# PIC.net
KiCad netlist of a schematic drawn in Altium Designer
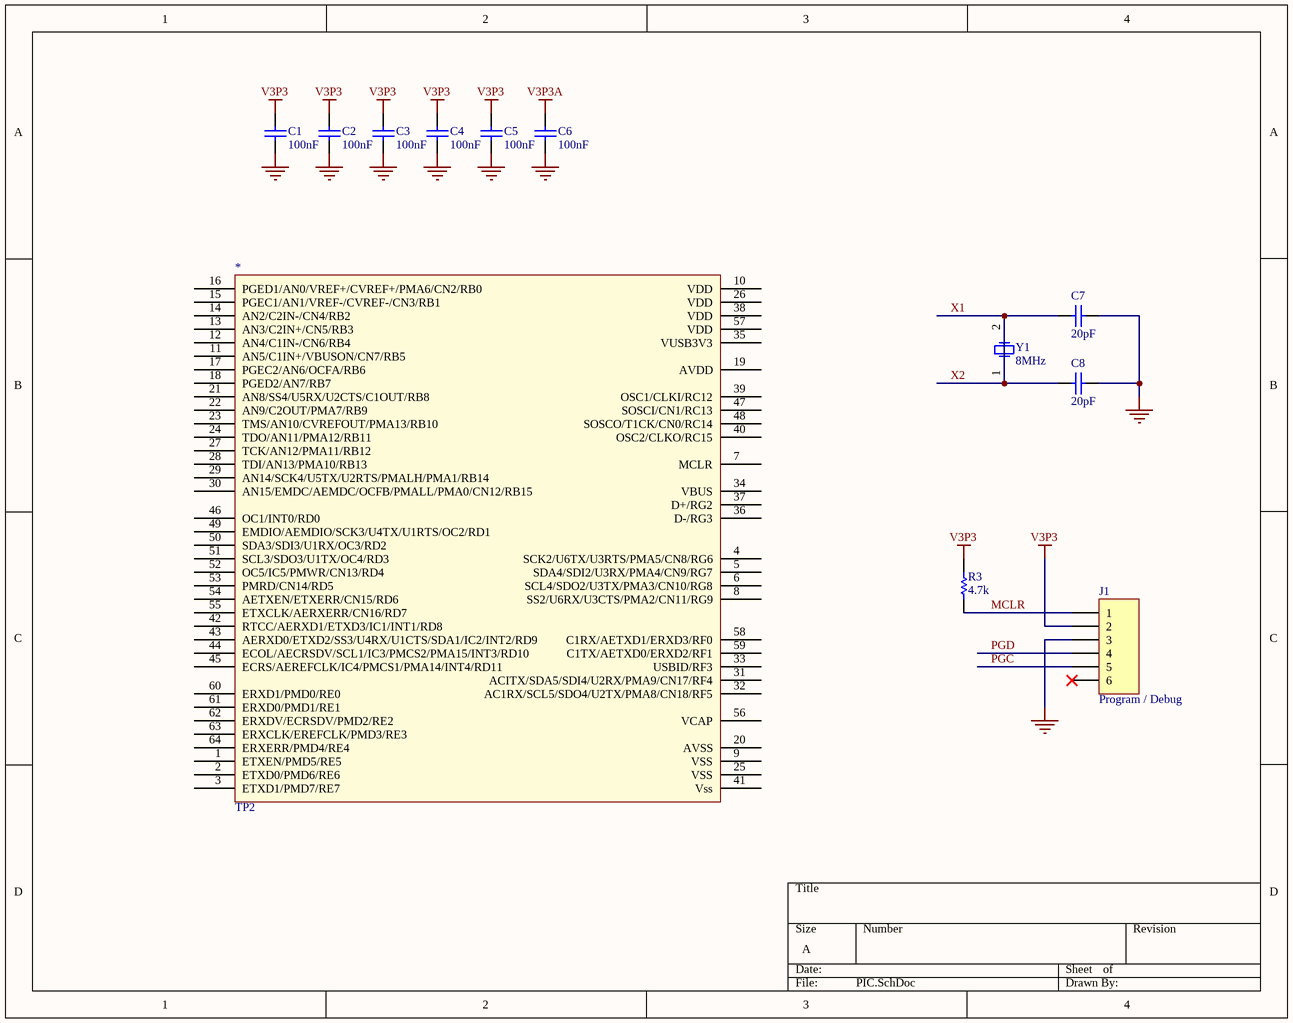
[diagram p0: PIC.SchDoc]

(export (version "E")
  (design (tool "Eeschema 10.0.6"))
  (components
    (comp (ref "*") (value "TP2") (libsource (lib "Rectangle-et-texte-PIC32") (part "TP2")))
    (comp (ref "C1")
      (value "100nF")
      (footprint "CAPC1608N")
      (description "Capacitor")
      (fields (field (name "PUBLISHER") "Altium Limited"))
      (libsource (lib "Miscellaneous Devices") (part "Cap"))
    )
    (comp (ref "C2")
      (value "100nF")
      (footprint "CAPC1608N")
      (description "Capacitor")
      (fields (field (name "PUBLISHER") "Altium Limited"))
      (libsource (lib "Miscellaneous Devices") (part "Cap"))
    )
    (comp (ref "C3")
      (value "100nF")
      (footprint "CAPC1608N")
      (description "Capacitor")
      (fields (field (name "PUBLISHER") "Altium Limited"))
      (libsource (lib "Miscellaneous Devices") (part "Cap"))
    )
    (comp (ref "C4")
      (value "100nF")
      (footprint "CAPC1608N")
      (description "Capacitor")
      (fields (field (name "PUBLISHER") "Altium Limited"))
      (libsource (lib "Miscellaneous Devices") (part "Cap"))
    )
    (comp (ref "C5")
      (value "100nF")
      (footprint "CAPC1608N")
      (description "Capacitor")
      (fields (field (name "PUBLISHER") "Altium Limited"))
      (libsource (lib "Miscellaneous Devices") (part "Cap"))
    )
    (comp (ref "C6")
      (value "100nF")
      (footprint "CAPC1608N")
      (description "Capacitor")
      (fields (field (name "PUBLISHER") "Altium Limited"))
      (libsource (lib "Miscellaneous Devices") (part "Cap"))
    )
    (comp (ref "C7")
      (value "20pF")
      (footprint "CAPC1005N")
      (description "Capacitor")
      (fields (field (name "PUBLISHER") "Altium Limited"))
      (libsource (lib "Miscellaneous Devices") (part "Cap"))
    )
    (comp (ref "C8")
      (value "20pF")
      (footprint "CAPC1005N")
      (description "Capacitor")
      (fields (field (name "PUBLISHER") "Altium Limited"))
      (libsource (lib "Miscellaneous Devices") (part "Cap"))
    )
    (comp (ref "J1")
      (value "Program / Debug")
      (footprint "MOLEX 6P 1.25 CMS")
      (description "Header, 6-Pin, Right Angle")
      (fields (field (name "PUBLISHER") "Altium Limited"))
      (libsource (lib "Miscellaneous Connectors") (part "Header 6H"))
    )
    (comp (ref "R3")
      (value "4.7k")
      (footprint "RESC1608N")
      (description "Resistor")
      (fields (field (name "PUBLISHER") "Altium Limited"))
      (libsource (lib "Miscellaneous Devices") (part "Res1"))
    )
    (comp (ref "Y1")
      (value "8MHz")
      (footprint "XTAL139X50X45")
      (description "Crystal Oscillator")
      (fields (field (name "PUBLISHER") "Altium Limited"))
      (libsource (lib "Miscellaneous Devices") (part "XTAL"))
    )
  )
  (nets
    (net (code "1") (name "/MCLR") (class "Default")
      (node (ref "J1") (pin "1") (pinfunction "1_1") (pintype "passive"))
      (node (ref "R3") (pin "1") (pinfunction "1_1") (pintype "passive"))
    )
    (net (code "2") (name "/PGC") (class "Default")
      (node (ref "J1") (pin "5") (pinfunction "5_5") (pintype "passive"))
    )
    (net (code "3") (name "/PGD") (class "Default")
      (node (ref "J1") (pin "4") (pinfunction "4_4") (pintype "passive"))
    )
    (net (code "4") (name "/X1") (class "Default")
      (node (ref "C7") (pin "1") (pinfunction "1_1") (pintype "passive"))
      (node (ref "C8") (pin "1") (pinfunction "1_1") (pintype "passive"))
      (node (ref "Y1") (pin "1") (pinfunction "OSC1_1") (pintype "passive"))
      (node (ref "Y1") (pin "2") (pinfunction "OSC2_2") (pintype "passive"))
    )
    (net (code "5") (name "GND") (class "Default")
      (node (ref "C1") (pin "1") (pinfunction "1_1") (pintype "passive"))
      (node (ref "C2") (pin "1") (pinfunction "1_1") (pintype "passive"))
      (node (ref "C3") (pin "1") (pinfunction "1_1") (pintype "passive"))
      (node (ref "C4") (pin "1") (pinfunction "1_1") (pintype "passive"))
      (node (ref "C5") (pin "1") (pinfunction "1_1") (pintype "passive"))
      (node (ref "C6") (pin "1") (pinfunction "1_1") (pintype "passive"))
      (node (ref "C7") (pin "2") (pinfunction "2_2") (pintype "passive"))
      (node (ref "C8") (pin "2") (pinfunction "2_2") (pintype "passive"))
      (node (ref "J1") (pin "3") (pinfunction "3_3") (pintype "passive"))
    )
    (net (code "6") (name "V3P3") (class "Default")
      (node (ref "C1") (pin "2") (pinfunction "2_2") (pintype "passive"))
      (node (ref "C2") (pin "2") (pinfunction "2_2") (pintype "passive"))
      (node (ref "C3") (pin "2") (pinfunction "2_2") (pintype "passive"))
      (node (ref "C4") (pin "2") (pinfunction "2_2") (pintype "passive"))
      (node (ref "C5") (pin "2") (pinfunction "2_2") (pintype "passive"))
      (node (ref "J1") (pin "2") (pinfunction "2_2") (pintype "passive"))
      (node (ref "R3") (pin "2") (pinfunction "2_2") (pintype "passive"))
    )
    (net (code "7") (name "V3P3A") (class "Default")
      (node (ref "C6") (pin "2") (pinfunction "2_2") (pintype "passive"))
    )
    (net (code "8") (name "unconnected-(*-AC1RX{slash}SCL5{slash}SDO4{slash}U2TX{slash}PMA8{slash}CN18{slash}RF5-Pad32)") (class "Default")
      (node (ref "*") (pin "32") (pinfunction "AC1RX/SCL5/SDO4/U2TX/PMA8/CN18/RF5_32") (pintype "passive"))
    )
    (net (code "9") (name "unconnected-(*-ACITX{slash}SDA5{slash}SDI4{slash}U2RX{slash}PMA9{slash}CN17{slash}RF4-Pad31)") (class "Default")
      (node (ref "*") (pin "31") (pinfunction "ACITX/SDA5/SDI4/U2RX/PMA9/CN17/RF4_31") (pintype "passive"))
    )
    (net (code "10") (name "unconnected-(*-AERXD0{slash}ETXD2{slash}SS3{slash}U4RX{slash}U1CTS{slash}SDA1{slash}IC2{slash}INT2{slash}RD9-Pad43)") (class "Default")
      (node (ref "*") (pin "43") (pinfunction "AERXD0/ETXD2/SS3/U4RX/U1CTS/SDA1/IC2/INT2/RD9_43") (pintype "passive"))
    )
    (net (code "11") (name "unconnected-(*-AETXEN{slash}ETXERR{slash}CN15{slash}RD6-Pad54)") (class "Default")
      (node (ref "*") (pin "54") (pinfunction "AETXEN/ETXERR/CN15/RD6_54") (pintype "passive"))
    )
    (net (code "12") (name "unconnected-(*-AN2{slash}C2IN-{slash}CN4{slash}RB2-Pad14)") (class "Default")
      (node (ref "*") (pin "14") (pinfunction "AN2/C2IN-/CN4/RB2_14") (pintype "passive"))
    )
    (net (code "13") (name "unconnected-(*-AN3{slash}C2IN+{slash}CN5{slash}RB3-Pad13)") (class "Default")
      (node (ref "*") (pin "13") (pinfunction "AN3/C2IN+/CN5/RB3_13") (pintype "passive"))
    )
    (net (code "14") (name "unconnected-(*-AN4{slash}C1IN-{slash}CN6{slash}RB4-Pad12)") (class "Default")
      (node (ref "*") (pin "12") (pinfunction "AN4/C1IN-/CN6/RB4_12") (pintype "passive"))
    )
    (net (code "15") (name "unconnected-(*-AN5{slash}C1IN+{slash}VBUSON{slash}CN7{slash}RB5-Pad11)") (class "Default")
      (node (ref "*") (pin "11") (pinfunction "AN5/C1IN+/VBUSON/CN7/RB5_11") (pintype "passive"))
    )
    (net (code "16") (name "unconnected-(*-AN8{slash}SS4{slash}U5RX{slash}U2CTS{slash}C1OUT{slash}RB8-Pad21)") (class "Default")
      (node (ref "*") (pin "21") (pinfunction "AN8/SS4/U5RX/U2CTS/C1OUT/RB8_21") (pintype "passive"))
    )
    (net (code "17") (name "unconnected-(*-AN9{slash}C2OUT{slash}PMA7{slash}RB9-Pad22)") (class "Default")
      (node (ref "*") (pin "22") (pinfunction "AN9/C2OUT/PMA7/RB9_22") (pintype "passive"))
    )
    (net (code "18") (name "unconnected-(*-AN14{slash}SCK4{slash}U5TX{slash}U2RTS{slash}PMALH{slash}PMA1{slash}RB14-Pad29)") (class "Default")
      (node (ref "*") (pin "29") (pinfunction "AN14/SCK4/U5TX/U2RTS/PMALH/PMA1/RB14_29") (pintype "passive"))
    )
    (net (code "19") (name "unconnected-(*-AN15{slash}EMDC{slash}AEMDC{slash}OCFB{slash}PMALL{slash}PMA0{slash}CN12{slash}RB15-Pad30)") (class "Default")
      (node (ref "*") (pin "30") (pinfunction "AN15/EMDC/AEMDC/OCFB/PMALL/PMA0/CN12/RB15_30") (pintype "passive"))
    )
    (net (code "20") (name "unconnected-(*-AVDD-Pad19)") (class "Default")
      (node (ref "*") (pin "19") (pinfunction "AVDD_19") (pintype "passive"))
    )
    (net (code "21") (name "unconnected-(*-AVSS-Pad20)") (class "Default")
      (node (ref "*") (pin "20") (pinfunction "AVSS_20") (pintype "passive"))
    )
    (net (code "22") (name "unconnected-(*-C1RX{slash}AETXD1{slash}ERXD3{slash}RF0-Pad58)") (class "Default")
      (node (ref "*") (pin "58") (pinfunction "C1RX/AETXD1/ERXD3/RF0_58") (pintype "passive"))
    )
    (net (code "23") (name "unconnected-(*-C1TX{slash}AETXD0{slash}ERXD2{slash}RF1-Pad59)") (class "Default")
      (node (ref "*") (pin "59") (pinfunction "C1TX/AETXD0/ERXD2/RF1_59") (pintype "passive"))
    )
    (net (code "24") (name "unconnected-(*-D+{slash}RG2-Pad37)") (class "Default")
      (node (ref "*") (pin "37") (pinfunction "D+/RG2_37") (pintype "passive"))
    )
    (net (code "25") (name "unconnected-(*-D-{slash}RG3-Pad36)") (class "Default")
      (node (ref "*") (pin "36") (pinfunction "D-/RG3_36") (pintype "passive"))
    )
    (net (code "26") (name "unconnected-(*-ECOL{slash}AECRSDV{slash}SCL1{slash}IC3{slash}PMCS2{slash}PMA15{slash}INT3{slash}RD10-Pad44)") (class "Default")
      (node (ref "*") (pin "44") (pinfunction "ECOL/AECRSDV/SCL1/IC3/PMCS2/PMA15/INT3/RD10_44") (pintype "passive"))
    )
    (net (code "27") (name "unconnected-(*-ECRS{slash}AEREFCLK{slash}IC4{slash}PMCS1{slash}PMA14{slash}INT4{slash}RD11-Pad45)") (class "Default")
      (node (ref "*") (pin "45") (pinfunction "ECRS/AEREFCLK/IC4/PMCS1/PMA14/INT4/RD11_45") (pintype "passive"))
    )
    (net (code "28") (name "unconnected-(*-EMDIO{slash}AEMDIO{slash}SCK3{slash}U4TX{slash}U1RTS{slash}OC2{slash}RD1-Pad49)") (class "Default")
      (node (ref "*") (pin "49") (pinfunction "EMDIO/AEMDIO/SCK3/U4TX/U1RTS/OC2/RD1_49") (pintype "passive"))
    )
    (net (code "29") (name "unconnected-(*-ERXCLK{slash}EREFCLK{slash}PMD3{slash}RE3-Pad63)") (class "Default")
      (node (ref "*") (pin "63") (pinfunction "ERXCLK/EREFCLK/PMD3/RE3_63") (pintype "passive"))
    )
    (net (code "30") (name "unconnected-(*-ERXD0{slash}PMD1{slash}RE1-Pad61)") (class "Default")
      (node (ref "*") (pin "61") (pinfunction "ERXD0/PMD1/RE1_61") (pintype "passive"))
    )
    (net (code "31") (name "unconnected-(*-ERXD1{slash}PMD0{slash}RE0-Pad60)") (class "Default")
      (node (ref "*") (pin "60") (pinfunction "ERXD1/PMD0/RE0_60") (pintype "passive"))
    )
    (net (code "32") (name "unconnected-(*-ERXDV{slash}ECRSDV{slash}PMD2{slash}RE2-Pad62)") (class "Default")
      (node (ref "*") (pin "62") (pinfunction "ERXDV/ECRSDV/PMD2/RE2_62") (pintype "passive"))
    )
    (net (code "33") (name "unconnected-(*-ERXERR{slash}PMD4{slash}RE4-Pad64)") (class "Default")
      (node (ref "*") (pin "64") (pinfunction "ERXERR/PMD4/RE4_64") (pintype "passive"))
    )
    (net (code "34") (name "unconnected-(*-ETXCLK{slash}AERXERR{slash}CN16{slash}RD7-Pad55)") (class "Default")
      (node (ref "*") (pin "55") (pinfunction "ETXCLK/AERXERR/CN16/RD7_55") (pintype "passive"))
    )
    (net (code "35") (name "unconnected-(*-ETXD0{slash}PMD6{slash}RE6-Pad2)") (class "Default")
      (node (ref "*") (pin "2") (pinfunction "ETXD0/PMD6/RE6_2") (pintype "passive"))
    )
    (net (code "36") (name "unconnected-(*-ETXD1{slash}PMD7{slash}RE7-Pad3)") (class "Default")
      (node (ref "*") (pin "3") (pinfunction "ETXD1/PMD7/RE7_3") (pintype "passive"))
    )
    (net (code "37") (name "unconnected-(*-ETXEN{slash}PMD5{slash}RE5-Pad1)") (class "Default")
      (node (ref "*") (pin "1") (pinfunction "ETXEN/PMD5/RE5_1") (pintype "passive"))
    )
    (net (code "38") (name "unconnected-(*-MCLR-Pad7)") (class "Default")
      (node (ref "*") (pin "7") (pinfunction "MCLR_7") (pintype "passive"))
    )
    (net (code "39") (name "unconnected-(*-OC1{slash}INT0{slash}RD0-Pad46)") (class "Default")
      (node (ref "*") (pin "46") (pinfunction "OC1/INT0/RD0_46") (pintype "passive"))
    )
    (net (code "40") (name "unconnected-(*-OC5{slash}IC5{slash}PMWR{slash}CN13{slash}RD4-Pad52)") (class "Default")
      (node (ref "*") (pin "52") (pinfunction "OC5/IC5/PMWR/CN13/RD4_52") (pintype "passive"))
    )
    (net (code "41") (name "unconnected-(*-OSC1{slash}CLKI{slash}RC12-Pad39)") (class "Default")
      (node (ref "*") (pin "39") (pinfunction "OSC1/CLKI/RC12_39") (pintype "passive"))
    )
    (net (code "42") (name "unconnected-(*-OSC2{slash}CLKO{slash}RC15-Pad40)") (class "Default")
      (node (ref "*") (pin "40") (pinfunction "OSC2/CLKO/RC15_40") (pintype "passive"))
    )
    (net (code "43") (name "unconnected-(*-PGEC1{slash}AN1{slash}VREF-{slash}CVREF-{slash}CN3{slash}RB1-Pad15)") (class "Default")
      (node (ref "*") (pin "15") (pinfunction "PGEC1/AN1/VREF-/CVREF-/CN3/RB1_15") (pintype "passive"))
    )
    (net (code "44") (name "unconnected-(*-PGEC2{slash}AN6{slash}OCFA{slash}RB6-Pad17)") (class "Default")
      (node (ref "*") (pin "17") (pinfunction "PGEC2/AN6/OCFA/RB6_17") (pintype "passive"))
    )
    (net (code "45") (name "unconnected-(*-PGED1{slash}AN0{slash}VREF+{slash}CVREF+{slash}PMA6{slash}CN2{slash}RB0-Pad16)") (class "Default")
      (node (ref "*") (pin "16") (pinfunction "PGED1/AN0/VREF+/CVREF+/PMA6/CN2/RB0_16") (pintype "passive"))
    )
    (net (code "46") (name "unconnected-(*-PGED2{slash}AN7{slash}RB7-Pad18)") (class "Default")
      (node (ref "*") (pin "18") (pinfunction "PGED2/AN7/RB7_18") (pintype "passive"))
    )
    (net (code "47") (name "unconnected-(*-PMRD{slash}CN14{slash}RD5-Pad53)") (class "Default")
      (node (ref "*") (pin "53") (pinfunction "PMRD/CN14/RD5_53") (pintype "passive"))
    )
    (net (code "48") (name "unconnected-(*-RTCC{slash}AERXD1{slash}ETXD3{slash}IC1{slash}INT1{slash}RD8-Pad42)") (class "Default")
      (node (ref "*") (pin "42") (pinfunction "RTCC/AERXD1/ETXD3/IC1/INT1/RD8_42") (pintype "passive"))
    )
    (net (code "49") (name "unconnected-(*-SCK2{slash}U6TX{slash}U3RTS{slash}PMA5{slash}CN8{slash}RG6-Pad4)") (class "Default")
      (node (ref "*") (pin "4") (pinfunction "SCK2/U6TX/U3RTS/PMA5/CN8/RG6_4") (pintype "passive"))
    )
    (net (code "50") (name "unconnected-(*-SCL3{slash}SDO3{slash}U1TX{slash}OC4{slash}RD3-Pad51)") (class "Default")
      (node (ref "*") (pin "51") (pinfunction "SCL3/SDO3/U1TX/OC4/RD3_51") (pintype "passive"))
    )
    (net (code "51") (name "unconnected-(*-SCL4{slash}SDO2{slash}U3TX{slash}PMA3{slash}CN10{slash}RG8-Pad6)") (class "Default")
      (node (ref "*") (pin "6") (pinfunction "SCL4/SDO2/U3TX/PMA3/CN10/RG8_6") (pintype "passive"))
    )
    (net (code "52") (name "unconnected-(*-SDA3{slash}SDI3{slash}U1RX{slash}OC3{slash}RD2-Pad50)") (class "Default")
      (node (ref "*") (pin "50") (pinfunction "SDA3/SDI3/U1RX/OC3/RD2_50") (pintype "passive"))
    )
    (net (code "53") (name "unconnected-(*-SDA4{slash}SDI2{slash}U3RX{slash}PMA4{slash}CN9{slash}RG7-Pad5)") (class "Default")
      (node (ref "*") (pin "5") (pinfunction "SDA4/SDI2/U3RX/PMA4/CN9/RG7_5") (pintype "passive"))
    )
    (net (code "54") (name "unconnected-(*-SOSCI{slash}CN1{slash}RC13-Pad47)") (class "Default")
      (node (ref "*") (pin "47") (pinfunction "SOSCI/CN1/RC13_47") (pintype "passive"))
    )
    (net (code "55") (name "unconnected-(*-SOSCO{slash}T1CK{slash}CN0{slash}RC14-Pad48)") (class "Default")
      (node (ref "*") (pin "48") (pinfunction "SOSCO/T1CK/CN0/RC14_48") (pintype "passive"))
    )
    (net (code "56") (name "unconnected-(*-SS2{slash}U6RX{slash}U3CTS{slash}PMA2{slash}CN11{slash}RG9-Pad8)") (class "Default")
      (node (ref "*") (pin "8") (pinfunction "SS2/U6RX/U3CTS/PMA2/CN11/RG9_8") (pintype "passive"))
    )
    (net (code "57") (name "unconnected-(*-TCK{slash}AN12{slash}PMA11{slash}RB12-Pad27)") (class "Default")
      (node (ref "*") (pin "27") (pinfunction "TCK/AN12/PMA11/RB12_27") (pintype "passive"))
    )
    (net (code "58") (name "unconnected-(*-TDI{slash}AN13{slash}PMA10{slash}RB13-Pad28)") (class "Default")
      (node (ref "*") (pin "28") (pinfunction "TDI/AN13/PMA10/RB13_28") (pintype "passive"))
    )
    (net (code "59") (name "unconnected-(*-TDO{slash}AN11{slash}PMA12{slash}RB11-Pad24)") (class "Default")
      (node (ref "*") (pin "24") (pinfunction "TDO/AN11/PMA12/RB11_24") (pintype "passive"))
    )
    (net (code "60") (name "unconnected-(*-TMS{slash}AN10{slash}CVREFOUT{slash}PMA13{slash}RB10-Pad23)") (class "Default")
      (node (ref "*") (pin "23") (pinfunction "TMS/AN10/CVREFOUT/PMA13/RB10_23") (pintype "passive"))
    )
    (net (code "61") (name "unconnected-(*-USBID{slash}RF3-Pad33)") (class "Default")
      (node (ref "*") (pin "33") (pinfunction "USBID/RF3_33") (pintype "passive"))
    )
    (net (code "62") (name "unconnected-(*-VBUS-Pad34)") (class "Default")
      (node (ref "*") (pin "34") (pinfunction "VBUS_34") (pintype "passive"))
    )
    (net (code "63") (name "unconnected-(*-VCAP-Pad56)") (class "Default")
      (node (ref "*") (pin "56") (pinfunction "VCAP_56") (pintype "passive"))
    )
    (net (code "64") (name "unconnected-(*-VDD-Pad10)") (class "Default")
      (node (ref "*") (pin "10") (pinfunction "VDD_10") (pintype "passive"))
    )
    (net (code "65") (name "unconnected-(*-VDD-Pad26)") (class "Default")
      (node (ref "*") (pin "26") (pinfunction "VDD_26") (pintype "passive"))
    )
    (net (code "66") (name "unconnected-(*-VDD-Pad38)") (class "Default")
      (node (ref "*") (pin "38") (pinfunction "VDD_38") (pintype "passive"))
    )
    (net (code "67") (name "unconnected-(*-VDD-Pad57)") (class "Default")
      (node (ref "*") (pin "57") (pinfunction "VDD_57") (pintype "passive"))
    )
    (net (code "68") (name "unconnected-(*-VSS-Pad9)") (class "Default")
      (node (ref "*") (pin "9") (pinfunction "VSS_9") (pintype "passive"))
    )
    (net (code "69") (name "unconnected-(*-VSS-Pad25)") (class "Default")
      (node (ref "*") (pin "25") (pinfunction "VSS_25") (pintype "passive"))
    )
    (net (code "70") (name "unconnected-(*-VUSB3V3-Pad35)") (class "Default")
      (node (ref "*") (pin "35") (pinfunction "VUSB3V3_35") (pintype "passive"))
    )
    (net (code "71") (name "unconnected-(*-Vss-Pad41)") (class "Default")
      (node (ref "*") (pin "41") (pinfunction "Vss_41") (pintype "passive"))
    )
    (net (code "72") (name "unconnected-(J1-Pad6)") (class "Default")
      (node (ref "J1") (pin "6") (pinfunction "6_6") (pintype "passive+no_connect"))
    )
  )
)
